# perf_board_schematic.net
KiCad netlist of a schematic drawn in Altium Designer
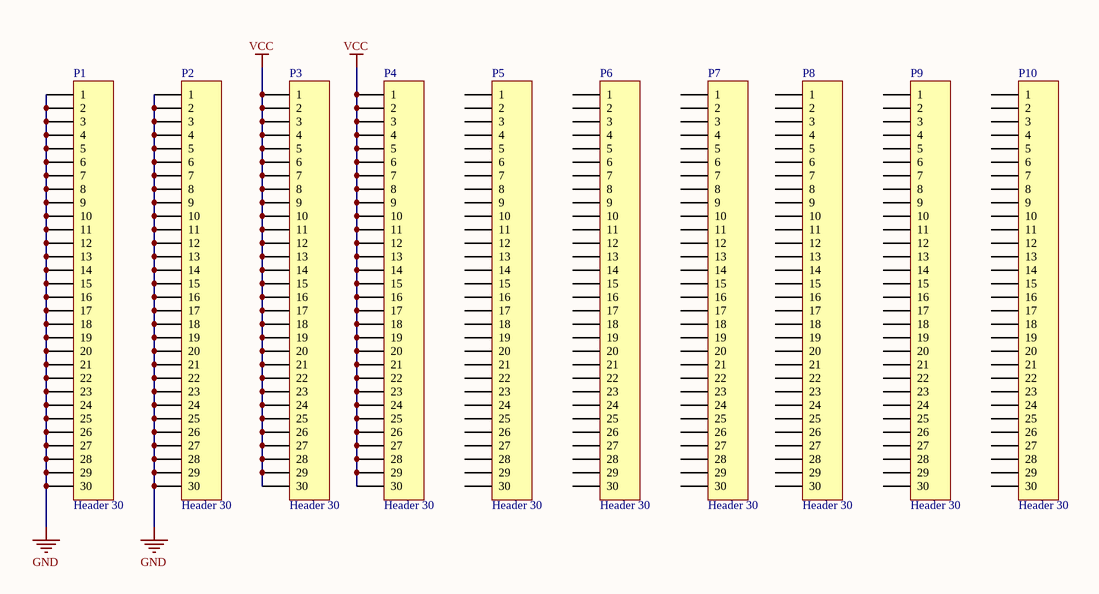
[diagram p0: perf_board_schematic.SchDoc]

(export (version "E")
  (design (tool "Eeschema 10.0.6"))
  (components
    (comp (ref "P1")
      (value "Header 30")
      (footprint "HDR1X30")
      (description "Header, 30-Pin")
      (fields (field (name "PUBLISHER") "Altium Limited"))
      (libsource (lib "Miscellaneous Connectors") (part "Header 30"))
    )
    (comp (ref "P2")
      (value "Header 30")
      (footprint "HDR1X30")
      (description "Header, 30-Pin")
      (fields (field (name "PUBLISHER") "Altium Limited"))
      (libsource (lib "Miscellaneous Connectors") (part "Header 30"))
    )
    (comp (ref "P3")
      (value "Header 30")
      (footprint "HDR1X30")
      (description "Header, 30-Pin")
      (fields (field (name "PUBLISHER") "Altium Limited"))
      (libsource (lib "Miscellaneous Connectors") (part "Header 30"))
    )
    (comp (ref "P4")
      (value "Header 30")
      (footprint "HDR1X30")
      (description "Header, 30-Pin")
      (fields (field (name "PUBLISHER") "Altium Limited"))
      (libsource (lib "Miscellaneous Connectors") (part "Header 30"))
    )
    (comp (ref "P5")
      (value "Header 30")
      (footprint "HDR1X30")
      (description "Header, 30-Pin")
      (fields (field (name "PUBLISHER") "Altium Limited"))
      (libsource (lib "Miscellaneous Connectors") (part "Header 30"))
    )
    (comp (ref "P6")
      (value "Header 30")
      (footprint "HDR1X30")
      (description "Header, 30-Pin")
      (fields (field (name "PUBLISHER") "Altium Limited"))
      (libsource (lib "Miscellaneous Connectors") (part "Header 30"))
    )
    (comp (ref "P7")
      (value "Header 30")
      (footprint "HDR1X30")
      (description "Header, 30-Pin")
      (fields (field (name "PUBLISHER") "Altium Limited"))
      (libsource (lib "Miscellaneous Connectors") (part "Header 30"))
    )
    (comp (ref "P8")
      (value "Header 30")
      (footprint "HDR1X30")
      (description "Header, 30-Pin")
      (fields (field (name "PUBLISHER") "Altium Limited"))
      (libsource (lib "Miscellaneous Connectors") (part "Header 30"))
    )
    (comp (ref "P9")
      (value "Header 30")
      (footprint "HDR1X30")
      (description "Header, 30-Pin")
      (fields (field (name "PUBLISHER") "Altium Limited"))
      (libsource (lib "Miscellaneous Connectors") (part "Header 30"))
    )
    (comp (ref "P10")
      (value "Header 30")
      (footprint "HDR1X30")
      (description "Header, 30-Pin")
      (fields (field (name "PUBLISHER") "Altium Limited"))
      (libsource (lib "Miscellaneous Connectors") (part "Header 30"))
    )
  )
  (nets
    (net (code "1") (name "GND") (class "Default")
      (node (ref "P1") (pin "1") (pinfunction "1_1") (pintype "passive"))
      (node (ref "P1") (pin "10") (pinfunction "10_10") (pintype "passive"))
      (node (ref "P1") (pin "11") (pinfunction "11_11") (pintype "passive"))
      (node (ref "P1") (pin "12") (pinfunction "12_12") (pintype "passive"))
      (node (ref "P1") (pin "13") (pinfunction "13_13") (pintype "passive"))
      (node (ref "P1") (pin "14") (pinfunction "14_14") (pintype "passive"))
      (node (ref "P1") (pin "15") (pinfunction "15_15") (pintype "passive"))
      (node (ref "P1") (pin "16") (pinfunction "16_16") (pintype "passive"))
      (node (ref "P1") (pin "17") (pinfunction "17_17") (pintype "passive"))
      (node (ref "P1") (pin "18") (pinfunction "18_18") (pintype "passive"))
      (node (ref "P1") (pin "19") (pinfunction "19_19") (pintype "passive"))
      (node (ref "P1") (pin "2") (pinfunction "2_2") (pintype "passive"))
      (node (ref "P1") (pin "20") (pinfunction "20_20") (pintype "passive"))
      (node (ref "P1") (pin "21") (pinfunction "21_21") (pintype "passive"))
      (node (ref "P1") (pin "22") (pinfunction "22_22") (pintype "passive"))
      (node (ref "P1") (pin "23") (pinfunction "23_23") (pintype "passive"))
      (node (ref "P1") (pin "24") (pinfunction "24_24") (pintype "passive"))
      (node (ref "P1") (pin "25") (pinfunction "25_25") (pintype "passive"))
      (node (ref "P1") (pin "26") (pinfunction "26_26") (pintype "passive"))
      (node (ref "P1") (pin "27") (pinfunction "27_27") (pintype "passive"))
      (node (ref "P1") (pin "28") (pinfunction "28_28") (pintype "passive"))
      (node (ref "P1") (pin "29") (pinfunction "29_29") (pintype "passive"))
      (node (ref "P1") (pin "3") (pinfunction "3_3") (pintype "passive"))
      (node (ref "P1") (pin "30") (pinfunction "30_30") (pintype "passive"))
      (node (ref "P1") (pin "4") (pinfunction "4_4") (pintype "passive"))
      (node (ref "P1") (pin "5") (pinfunction "5_5") (pintype "passive"))
      (node (ref "P1") (pin "6") (pinfunction "6_6") (pintype "passive"))
      (node (ref "P1") (pin "7") (pinfunction "7_7") (pintype "passive"))
      (node (ref "P1") (pin "8") (pinfunction "8_8") (pintype "passive"))
      (node (ref "P1") (pin "9") (pinfunction "9_9") (pintype "passive"))
      (node (ref "P2") (pin "1") (pinfunction "1_1") (pintype "passive"))
      (node (ref "P2") (pin "10") (pinfunction "10_10") (pintype "passive"))
      (node (ref "P2") (pin "11") (pinfunction "11_11") (pintype "passive"))
      (node (ref "P2") (pin "12") (pinfunction "12_12") (pintype "passive"))
      (node (ref "P2") (pin "13") (pinfunction "13_13") (pintype "passive"))
      (node (ref "P2") (pin "14") (pinfunction "14_14") (pintype "passive"))
      (node (ref "P2") (pin "15") (pinfunction "15_15") (pintype "passive"))
      (node (ref "P2") (pin "16") (pinfunction "16_16") (pintype "passive"))
      (node (ref "P2") (pin "17") (pinfunction "17_17") (pintype "passive"))
      (node (ref "P2") (pin "18") (pinfunction "18_18") (pintype "passive"))
      (node (ref "P2") (pin "19") (pinfunction "19_19") (pintype "passive"))
      (node (ref "P2") (pin "2") (pinfunction "2_2") (pintype "passive"))
      (node (ref "P2") (pin "20") (pinfunction "20_20") (pintype "passive"))
      (node (ref "P2") (pin "21") (pinfunction "21_21") (pintype "passive"))
      (node (ref "P2") (pin "22") (pinfunction "22_22") (pintype "passive"))
      (node (ref "P2") (pin "23") (pinfunction "23_23") (pintype "passive"))
      (node (ref "P2") (pin "24") (pinfunction "24_24") (pintype "passive"))
      (node (ref "P2") (pin "25") (pinfunction "25_25") (pintype "passive"))
      (node (ref "P2") (pin "26") (pinfunction "26_26") (pintype "passive"))
      (node (ref "P2") (pin "27") (pinfunction "27_27") (pintype "passive"))
      (node (ref "P2") (pin "28") (pinfunction "28_28") (pintype "passive"))
      (node (ref "P2") (pin "29") (pinfunction "29_29") (pintype "passive"))
      (node (ref "P2") (pin "3") (pinfunction "3_3") (pintype "passive"))
      (node (ref "P2") (pin "30") (pinfunction "30_30") (pintype "passive"))
      (node (ref "P2") (pin "4") (pinfunction "4_4") (pintype "passive"))
      (node (ref "P2") (pin "5") (pinfunction "5_5") (pintype "passive"))
      (node (ref "P2") (pin "6") (pinfunction "6_6") (pintype "passive"))
      (node (ref "P2") (pin "7") (pinfunction "7_7") (pintype "passive"))
      (node (ref "P2") (pin "8") (pinfunction "8_8") (pintype "passive"))
      (node (ref "P2") (pin "9") (pinfunction "9_9") (pintype "passive"))
    )
    (net (code "2") (name "VCC") (class "Default")
      (node (ref "P3") (pin "1") (pinfunction "1_1") (pintype "passive"))
      (node (ref "P3") (pin "10") (pinfunction "10_10") (pintype "passive"))
      (node (ref "P3") (pin "11") (pinfunction "11_11") (pintype "passive"))
      (node (ref "P3") (pin "12") (pinfunction "12_12") (pintype "passive"))
      (node (ref "P3") (pin "13") (pinfunction "13_13") (pintype "passive"))
      (node (ref "P3") (pin "14") (pinfunction "14_14") (pintype "passive"))
      (node (ref "P3") (pin "15") (pinfunction "15_15") (pintype "passive"))
      (node (ref "P3") (pin "16") (pinfunction "16_16") (pintype "passive"))
      (node (ref "P3") (pin "17") (pinfunction "17_17") (pintype "passive"))
      (node (ref "P3") (pin "18") (pinfunction "18_18") (pintype "passive"))
      (node (ref "P3") (pin "19") (pinfunction "19_19") (pintype "passive"))
      (node (ref "P3") (pin "2") (pinfunction "2_2") (pintype "passive"))
      (node (ref "P3") (pin "20") (pinfunction "20_20") (pintype "passive"))
      (node (ref "P3") (pin "21") (pinfunction "21_21") (pintype "passive"))
      (node (ref "P3") (pin "22") (pinfunction "22_22") (pintype "passive"))
      (node (ref "P3") (pin "23") (pinfunction "23_23") (pintype "passive"))
      (node (ref "P3") (pin "24") (pinfunction "24_24") (pintype "passive"))
      (node (ref "P3") (pin "25") (pinfunction "25_25") (pintype "passive"))
      (node (ref "P3") (pin "26") (pinfunction "26_26") (pintype "passive"))
      (node (ref "P3") (pin "27") (pinfunction "27_27") (pintype "passive"))
      (node (ref "P3") (pin "28") (pinfunction "28_28") (pintype "passive"))
      (node (ref "P3") (pin "29") (pinfunction "29_29") (pintype "passive"))
      (node (ref "P3") (pin "3") (pinfunction "3_3") (pintype "passive"))
      (node (ref "P3") (pin "30") (pinfunction "30_30") (pintype "passive"))
      (node (ref "P3") (pin "4") (pinfunction "4_4") (pintype "passive"))
      (node (ref "P3") (pin "5") (pinfunction "5_5") (pintype "passive"))
      (node (ref "P3") (pin "6") (pinfunction "6_6") (pintype "passive"))
      (node (ref "P3") (pin "7") (pinfunction "7_7") (pintype "passive"))
      (node (ref "P3") (pin "8") (pinfunction "8_8") (pintype "passive"))
      (node (ref "P3") (pin "9") (pinfunction "9_9") (pintype "passive"))
      (node (ref "P4") (pin "1") (pinfunction "1_1") (pintype "passive"))
      (node (ref "P4") (pin "10") (pinfunction "10_10") (pintype "passive"))
      (node (ref "P4") (pin "11") (pinfunction "11_11") (pintype "passive"))
      (node (ref "P4") (pin "12") (pinfunction "12_12") (pintype "passive"))
      (node (ref "P4") (pin "13") (pinfunction "13_13") (pintype "passive"))
      (node (ref "P4") (pin "14") (pinfunction "14_14") (pintype "passive"))
      (node (ref "P4") (pin "15") (pinfunction "15_15") (pintype "passive"))
      (node (ref "P4") (pin "16") (pinfunction "16_16") (pintype "passive"))
      (node (ref "P4") (pin "17") (pinfunction "17_17") (pintype "passive"))
      (node (ref "P4") (pin "18") (pinfunction "18_18") (pintype "passive"))
      (node (ref "P4") (pin "19") (pinfunction "19_19") (pintype "passive"))
      (node (ref "P4") (pin "2") (pinfunction "2_2") (pintype "passive"))
      (node (ref "P4") (pin "20") (pinfunction "20_20") (pintype "passive"))
      (node (ref "P4") (pin "21") (pinfunction "21_21") (pintype "passive"))
      (node (ref "P4") (pin "22") (pinfunction "22_22") (pintype "passive"))
      (node (ref "P4") (pin "23") (pinfunction "23_23") (pintype "passive"))
      (node (ref "P4") (pin "24") (pinfunction "24_24") (pintype "passive"))
      (node (ref "P4") (pin "25") (pinfunction "25_25") (pintype "passive"))
      (node (ref "P4") (pin "26") (pinfunction "26_26") (pintype "passive"))
      (node (ref "P4") (pin "27") (pinfunction "27_27") (pintype "passive"))
      (node (ref "P4") (pin "28") (pinfunction "28_28") (pintype "passive"))
      (node (ref "P4") (pin "29") (pinfunction "29_29") (pintype "passive"))
      (node (ref "P4") (pin "3") (pinfunction "3_3") (pintype "passive"))
      (node (ref "P4") (pin "30") (pinfunction "30_30") (pintype "passive"))
      (node (ref "P4") (pin "4") (pinfunction "4_4") (pintype "passive"))
      (node (ref "P4") (pin "5") (pinfunction "5_5") (pintype "passive"))
      (node (ref "P4") (pin "6") (pinfunction "6_6") (pintype "passive"))
      (node (ref "P4") (pin "7") (pinfunction "7_7") (pintype "passive"))
      (node (ref "P4") (pin "8") (pinfunction "8_8") (pintype "passive"))
      (node (ref "P4") (pin "9") (pinfunction "9_9") (pintype "passive"))
    )
    (net (code "3") (name "unconnected-(P5-Pad1)") (class "Default")
      (node (ref "P5") (pin "1") (pinfunction "1_1") (pintype "passive"))
    )
    (net (code "4") (name "unconnected-(P5-Pad2)") (class "Default")
      (node (ref "P5") (pin "2") (pinfunction "2_2") (pintype "passive"))
    )
    (net (code "5") (name "unconnected-(P5-Pad3)") (class "Default")
      (node (ref "P5") (pin "3") (pinfunction "3_3") (pintype "passive"))
    )
    (net (code "6") (name "unconnected-(P5-Pad4)") (class "Default")
      (node (ref "P5") (pin "4") (pinfunction "4_4") (pintype "passive"))
    )
    (net (code "7") (name "unconnected-(P5-Pad5)") (class "Default")
      (node (ref "P5") (pin "5") (pinfunction "5_5") (pintype "passive"))
    )
    (net (code "8") (name "unconnected-(P5-Pad6)") (class "Default")
      (node (ref "P5") (pin "6") (pinfunction "6_6") (pintype "passive"))
    )
    (net (code "9") (name "unconnected-(P5-Pad7)") (class "Default")
      (node (ref "P5") (pin "7") (pinfunction "7_7") (pintype "passive"))
    )
    (net (code "10") (name "unconnected-(P5-Pad8)") (class "Default")
      (node (ref "P5") (pin "8") (pinfunction "8_8") (pintype "passive"))
    )
    (net (code "11") (name "unconnected-(P5-Pad9)") (class "Default")
      (node (ref "P5") (pin "9") (pinfunction "9_9") (pintype "passive"))
    )
    (net (code "12") (name "unconnected-(P5-Pad10)") (class "Default")
      (node (ref "P5") (pin "10") (pinfunction "10_10") (pintype "passive"))
    )
    (net (code "13") (name "unconnected-(P5-Pad11)") (class "Default")
      (node (ref "P5") (pin "11") (pinfunction "11_11") (pintype "passive"))
    )
    (net (code "14") (name "unconnected-(P5-Pad12)") (class "Default")
      (node (ref "P5") (pin "12") (pinfunction "12_12") (pintype "passive"))
    )
    (net (code "15") (name "unconnected-(P5-Pad13)") (class "Default")
      (node (ref "P5") (pin "13") (pinfunction "13_13") (pintype "passive"))
    )
    (net (code "16") (name "unconnected-(P5-Pad14)") (class "Default")
      (node (ref "P5") (pin "14") (pinfunction "14_14") (pintype "passive"))
    )
    (net (code "17") (name "unconnected-(P5-Pad15)") (class "Default")
      (node (ref "P5") (pin "15") (pinfunction "15_15") (pintype "passive"))
    )
    (net (code "18") (name "unconnected-(P5-Pad16)") (class "Default")
      (node (ref "P5") (pin "16") (pinfunction "16_16") (pintype "passive"))
    )
    (net (code "19") (name "unconnected-(P5-Pad17)") (class "Default")
      (node (ref "P5") (pin "17") (pinfunction "17_17") (pintype "passive"))
    )
    (net (code "20") (name "unconnected-(P5-Pad18)") (class "Default")
      (node (ref "P5") (pin "18") (pinfunction "18_18") (pintype "passive"))
    )
    (net (code "21") (name "unconnected-(P5-Pad19)") (class "Default")
      (node (ref "P5") (pin "19") (pinfunction "19_19") (pintype "passive"))
    )
    (net (code "22") (name "unconnected-(P5-Pad20)") (class "Default")
      (node (ref "P5") (pin "20") (pinfunction "20_20") (pintype "passive"))
    )
    (net (code "23") (name "unconnected-(P5-Pad21)") (class "Default")
      (node (ref "P5") (pin "21") (pinfunction "21_21") (pintype "passive"))
    )
    (net (code "24") (name "unconnected-(P5-Pad22)") (class "Default")
      (node (ref "P5") (pin "22") (pinfunction "22_22") (pintype "passive"))
    )
    (net (code "25") (name "unconnected-(P5-Pad23)") (class "Default")
      (node (ref "P5") (pin "23") (pinfunction "23_23") (pintype "passive"))
    )
    (net (code "26") (name "unconnected-(P5-Pad24)") (class "Default")
      (node (ref "P5") (pin "24") (pinfunction "24_24") (pintype "passive"))
    )
    (net (code "27") (name "unconnected-(P5-Pad25)") (class "Default")
      (node (ref "P5") (pin "25") (pinfunction "25_25") (pintype "passive"))
    )
    (net (code "28") (name "unconnected-(P5-Pad26)") (class "Default")
      (node (ref "P5") (pin "26") (pinfunction "26_26") (pintype "passive"))
    )
    (net (code "29") (name "unconnected-(P5-Pad27)") (class "Default")
      (node (ref "P5") (pin "27") (pinfunction "27_27") (pintype "passive"))
    )
    (net (code "30") (name "unconnected-(P5-Pad28)") (class "Default")
      (node (ref "P5") (pin "28") (pinfunction "28_28") (pintype "passive"))
    )
    (net (code "31") (name "unconnected-(P5-Pad29)") (class "Default")
      (node (ref "P5") (pin "29") (pinfunction "29_29") (pintype "passive"))
    )
    (net (code "32") (name "unconnected-(P5-Pad30)") (class "Default")
      (node (ref "P5") (pin "30") (pinfunction "30_30") (pintype "passive"))
    )
    (net (code "33") (name "unconnected-(P6-Pad1)") (class "Default")
      (node (ref "P6") (pin "1") (pinfunction "1_1") (pintype "passive"))
    )
    (net (code "34") (name "unconnected-(P6-Pad2)") (class "Default")
      (node (ref "P6") (pin "2") (pinfunction "2_2") (pintype "passive"))
    )
    (net (code "35") (name "unconnected-(P6-Pad3)") (class "Default")
      (node (ref "P6") (pin "3") (pinfunction "3_3") (pintype "passive"))
    )
    (net (code "36") (name "unconnected-(P6-Pad4)") (class "Default")
      (node (ref "P6") (pin "4") (pinfunction "4_4") (pintype "passive"))
    )
    (net (code "37") (name "unconnected-(P6-Pad5)") (class "Default")
      (node (ref "P6") (pin "5") (pinfunction "5_5") (pintype "passive"))
    )
    (net (code "38") (name "unconnected-(P6-Pad6)") (class "Default")
      (node (ref "P6") (pin "6") (pinfunction "6_6") (pintype "passive"))
    )
    (net (code "39") (name "unconnected-(P6-Pad7)") (class "Default")
      (node (ref "P6") (pin "7") (pinfunction "7_7") (pintype "passive"))
    )
    (net (code "40") (name "unconnected-(P6-Pad8)") (class "Default")
      (node (ref "P6") (pin "8") (pinfunction "8_8") (pintype "passive"))
    )
    (net (code "41") (name "unconnected-(P6-Pad9)") (class "Default")
      (node (ref "P6") (pin "9") (pinfunction "9_9") (pintype "passive"))
    )
    (net (code "42") (name "unconnected-(P6-Pad10)") (class "Default")
      (node (ref "P6") (pin "10") (pinfunction "10_10") (pintype "passive"))
    )
    (net (code "43") (name "unconnected-(P6-Pad11)") (class "Default")
      (node (ref "P6") (pin "11") (pinfunction "11_11") (pintype "passive"))
    )
    (net (code "44") (name "unconnected-(P6-Pad12)") (class "Default")
      (node (ref "P6") (pin "12") (pinfunction "12_12") (pintype "passive"))
    )
    (net (code "45") (name "unconnected-(P6-Pad13)") (class "Default")
      (node (ref "P6") (pin "13") (pinfunction "13_13") (pintype "passive"))
    )
    (net (code "46") (name "unconnected-(P6-Pad14)") (class "Default")
      (node (ref "P6") (pin "14") (pinfunction "14_14") (pintype "passive"))
    )
    (net (code "47") (name "unconnected-(P6-Pad15)") (class "Default")
      (node (ref "P6") (pin "15") (pinfunction "15_15") (pintype "passive"))
    )
    (net (code "48") (name "unconnected-(P6-Pad16)") (class "Default")
      (node (ref "P6") (pin "16") (pinfunction "16_16") (pintype "passive"))
    )
    (net (code "49") (name "unconnected-(P6-Pad17)") (class "Default")
      (node (ref "P6") (pin "17") (pinfunction "17_17") (pintype "passive"))
    )
    (net (code "50") (name "unconnected-(P6-Pad18)") (class "Default")
      (node (ref "P6") (pin "18") (pinfunction "18_18") (pintype "passive"))
    )
    (net (code "51") (name "unconnected-(P6-Pad19)") (class "Default")
      (node (ref "P6") (pin "19") (pinfunction "19_19") (pintype "passive"))
    )
    (net (code "52") (name "unconnected-(P6-Pad20)") (class "Default")
      (node (ref "P6") (pin "20") (pinfunction "20_20") (pintype "passive"))
    )
    (net (code "53") (name "unconnected-(P6-Pad21)") (class "Default")
      (node (ref "P6") (pin "21") (pinfunction "21_21") (pintype "passive"))
    )
    (net (code "54") (name "unconnected-(P6-Pad22)") (class "Default")
      (node (ref "P6") (pin "22") (pinfunction "22_22") (pintype "passive"))
    )
    (net (code "55") (name "unconnected-(P6-Pad23)") (class "Default")
      (node (ref "P6") (pin "23") (pinfunction "23_23") (pintype "passive"))
    )
    (net (code "56") (name "unconnected-(P6-Pad24)") (class "Default")
      (node (ref "P6") (pin "24") (pinfunction "24_24") (pintype "passive"))
    )
    (net (code "57") (name "unconnected-(P6-Pad25)") (class "Default")
      (node (ref "P6") (pin "25") (pinfunction "25_25") (pintype "passive"))
    )
    (net (code "58") (name "unconnected-(P6-Pad26)") (class "Default")
      (node (ref "P6") (pin "26") (pinfunction "26_26") (pintype "passive"))
    )
    (net (code "59") (name "unconnected-(P6-Pad27)") (class "Default")
      (node (ref "P6") (pin "27") (pinfunction "27_27") (pintype "passive"))
    )
    (net (code "60") (name "unconnected-(P6-Pad28)") (class "Default")
      (node (ref "P6") (pin "28") (pinfunction "28_28") (pintype "passive"))
    )
    (net (code "61") (name "unconnected-(P6-Pad29)") (class "Default")
      (node (ref "P6") (pin "29") (pinfunction "29_29") (pintype "passive"))
    )
    (net (code "62") (name "unconnected-(P6-Pad30)") (class "Default")
      (node (ref "P6") (pin "30") (pinfunction "30_30") (pintype "passive"))
    )
    (net (code "63") (name "unconnected-(P7-Pad1)") (class "Default")
      (node (ref "P7") (pin "1") (pinfunction "1_1") (pintype "passive"))
    )
    (net (code "64") (name "unconnected-(P7-Pad2)") (class "Default")
      (node (ref "P7") (pin "2") (pinfunction "2_2") (pintype "passive"))
    )
    (net (code "65") (name "unconnected-(P7-Pad3)") (class "Default")
      (node (ref "P7") (pin "3") (pinfunction "3_3") (pintype "passive"))
    )
    (net (code "66") (name "unconnected-(P7-Pad4)") (class "Default")
      (node (ref "P7") (pin "4") (pinfunction "4_4") (pintype "passive"))
    )
    (net (code "67") (name "unconnected-(P7-Pad5)") (class "Default")
      (node (ref "P7") (pin "5") (pinfunction "5_5") (pintype "passive"))
    )
    (net (code "68") (name "unconnected-(P7-Pad6)") (class "Default")
      (node (ref "P7") (pin "6") (pinfunction "6_6") (pintype "passive"))
    )
    (net (code "69") (name "unconnected-(P7-Pad7)") (class "Default")
      (node (ref "P7") (pin "7") (pinfunction "7_7") (pintype "passive"))
    )
    (net (code "70") (name "unconnected-(P7-Pad8)") (class "Default")
      (node (ref "P7") (pin "8") (pinfunction "8_8") (pintype "passive"))
    )
    (net (code "71") (name "unconnected-(P7-Pad9)") (class "Default")
      (node (ref "P7") (pin "9") (pinfunction "9_9") (pintype "passive"))
    )
    (net (code "72") (name "unconnected-(P7-Pad10)") (class "Default")
      (node (ref "P7") (pin "10") (pinfunction "10_10") (pintype "passive"))
    )
    (net (code "73") (name "unconnected-(P7-Pad11)") (class "Default")
      (node (ref "P7") (pin "11") (pinfunction "11_11") (pintype "passive"))
    )
    (net (code "74") (name "unconnected-(P7-Pad12)") (class "Default")
      (node (ref "P7") (pin "12") (pinfunction "12_12") (pintype "passive"))
    )
    (net (code "75") (name "unconnected-(P7-Pad13)") (class "Default")
      (node (ref "P7") (pin "13") (pinfunction "13_13") (pintype "passive"))
    )
    (net (code "76") (name "unconnected-(P7-Pad14)") (class "Default")
      (node (ref "P7") (pin "14") (pinfunction "14_14") (pintype "passive"))
    )
    (net (code "77") (name "unconnected-(P7-Pad15)") (class "Default")
      (node (ref "P7") (pin "15") (pinfunction "15_15") (pintype "passive"))
    )
    (net (code "78") (name "unconnected-(P7-Pad16)") (class "Default")
      (node (ref "P7") (pin "16") (pinfunction "16_16") (pintype "passive"))
    )
    (net (code "79") (name "unconnected-(P7-Pad17)") (class "Default")
      (node (ref "P7") (pin "17") (pinfunction "17_17") (pintype "passive"))
    )
    (net (code "80") (name "unconnected-(P7-Pad18)") (class "Default")
      (node (ref "P7") (pin "18") (pinfunction "18_18") (pintype "passive"))
    )
    (net (code "81") (name "unconnected-(P7-Pad19)") (class "Default")
      (node (ref "P7") (pin "19") (pinfunction "19_19") (pintype "passive"))
    )
    (net (code "82") (name "unconnected-(P7-Pad20)") (class "Default")
      (node (ref "P7") (pin "20") (pinfunction "20_20") (pintype "passive"))
    )
    (net (code "83") (name "unconnected-(P7-Pad21)") (class "Default")
      (node (ref "P7") (pin "21") (pinfunction "21_21") (pintype "passive"))
    )
    (net (code "84") (name "unconnected-(P7-Pad22)") (class "Default")
      (node (ref "P7") (pin "22") (pinfunction "22_22") (pintype "passive"))
    )
    (net (code "85") (name "unconnected-(P7-Pad23)") (class "Default")
      (node (ref "P7") (pin "23") (pinfunction "23_23") (pintype "passive"))
    )
    (net (code "86") (name "unconnected-(P7-Pad24)") (class "Default")
      (node (ref "P7") (pin "24") (pinfunction "24_24") (pintype "passive"))
    )
    (net (code "87") (name "unconnected-(P7-Pad25)") (class "Default")
      (node (ref "P7") (pin "25") (pinfunction "25_25") (pintype "passive"))
    )
    (net (code "88") (name "unconnected-(P7-Pad26)") (class "Default")
      (node (ref "P7") (pin "26") (pinfunction "26_26") (pintype "passive"))
    )
    (net (code "89") (name "unconnected-(P7-Pad27)") (class "Default")
      (node (ref "P7") (pin "27") (pinfunction "27_27") (pintype "passive"))
    )
    (net (code "90") (name "unconnected-(P7-Pad28)") (class "Default")
      (node (ref "P7") (pin "28") (pinfunction "28_28") (pintype "passive"))
    )
    (net (code "91") (name "unconnected-(P7-Pad29)") (class "Default")
      (node (ref "P7") (pin "29") (pinfunction "29_29") (pintype "passive"))
    )
    (net (code "92") (name "unconnected-(P7-Pad30)") (class "Default")
      (node (ref "P7") (pin "30") (pinfunction "30_30") (pintype "passive"))
    )
    (net (code "93") (name "unconnected-(P8-Pad1)") (class "Default")
      (node (ref "P8") (pin "1") (pinfunction "1_1") (pintype "passive"))
    )
    (net (code "94") (name "unconnected-(P8-Pad2)") (class "Default")
      (node (ref "P8") (pin "2") (pinfunction "2_2") (pintype "passive"))
    )
    (net (code "95") (name "unconnected-(P8-Pad3)") (class "Default")
      (node (ref "P8") (pin "3") (pinfunction "3_3") (pintype "passive"))
    )
    (net (code "96") (name "unconnected-(P8-Pad4)") (class "Default")
      (node (ref "P8") (pin "4") (pinfunction "4_4") (pintype "passive"))
    )
    (net (code "97") (name "unconnected-(P8-Pad5)") (class "Default")
      (node (ref "P8") (pin "5") (pinfunction "5_5") (pintype "passive"))
    )
    (net (code "98") (name "unconnected-(P8-Pad6)") (class "Default")
      (node (ref "P8") (pin "6") (pinfunction "6_6") (pintype "passive"))
    )
    (net (code "99") (name "unconnected-(P8-Pad7)") (class "Default")
      (node (ref "P8") (pin "7") (pinfunction "7_7") (pintype "passive"))
    )
    (net (code "100") (name "unconnected-(P8-Pad8)") (class "Default")
      (node (ref "P8") (pin "8") (pinfunction "8_8") (pintype "passive"))
    )
    (net (code "101") (name "unconnected-(P8-Pad9)") (class "Default")
      (node (ref "P8") (pin "9") (pinfunction "9_9") (pintype "passive"))
    )
    (net (code "102") (name "unconnected-(P8-Pad10)") (class "Default")
      (node (ref "P8") (pin "10") (pinfunction "10_10") (pintype "passive"))
    )
    (net (code "103") (name "unconnected-(P8-Pad11)") (class "Default")
      (node (ref "P8") (pin "11") (pinfunction "11_11") (pintype "passive"))
    )
    (net (code "104") (name "unconnected-(P8-Pad12)") (class "Default")
      (node (ref "P8") (pin "12") (pinfunction "12_12") (pintype "passive"))
    )
    (net (code "105") (name "unconnected-(P8-Pad13)") (class "Default")
      (node (ref "P8") (pin "13") (pinfunction "13_13") (pintype "passive"))
    )
    (net (code "106") (name "unconnected-(P8-Pad14)") (class "Default")
      (node (ref "P8") (pin "14") (pinfunction "14_14") (pintype "passive"))
    )
    (net (code "107") (name "unconnected-(P8-Pad15)") (class "Default")
      (node (ref "P8") (pin "15") (pinfunction "15_15") (pintype "passive"))
    )
    (net (code "108") (name "unconnected-(P8-Pad16)") (class "Default")
      (node (ref "P8") (pin "16") (pinfunction "16_16") (pintype "passive"))
    )
    (net (code "109") (name "unconnected-(P8-Pad17)") (class "Default")
      (node (ref "P8") (pin "17") (pinfunction "17_17") (pintype "passive"))
    )
    (net (code "110") (name "unconnected-(P8-Pad18)") (class "Default")
      (node (ref "P8") (pin "18") (pinfunction "18_18") (pintype "passive"))
    )
    (net (code "111") (name "unconnected-(P8-Pad19)") (class "Default")
      (node (ref "P8") (pin "19") (pinfunction "19_19") (pintype "passive"))
    )
    (net (code "112") (name "unconnected-(P8-Pad20)") (class "Default")
      (node (ref "P8") (pin "20") (pinfunction "20_20") (pintype "passive"))
    )
    (net (code "113") (name "unconnected-(P8-Pad21)") (class "Default")
      (node (ref "P8") (pin "21") (pinfunction "21_21") (pintype "passive"))
    )
    (net (code "114") (name "unconnected-(P8-Pad22)") (class "Default")
      (node (ref "P8") (pin "22") (pinfunction "22_22") (pintype "passive"))
    )
    (net (code "115") (name "unconnected-(P8-Pad23)") (class "Default")
      (node (ref "P8") (pin "23") (pinfunction "23_23") (pintype "passive"))
    )
    (net (code "116") (name "unconnected-(P8-Pad24)") (class "Default")
      (node (ref "P8") (pin "24") (pinfunction "24_24") (pintype "passive"))
    )
    (net (code "117") (name "unconnected-(P8-Pad25)") (class "Default")
      (node (ref "P8") (pin "25") (pinfunction "25_25") (pintype "passive"))
    )
    (net (code "118") (name "unconnected-(P8-Pad26)") (class "Default")
      (node (ref "P8") (pin "26") (pinfunction "26_26") (pintype "passive"))
    )
    (net (code "119") (name "unconnected-(P8-Pad27)") (class "Default")
      (node (ref "P8") (pin "27") (pinfunction "27_27") (pintype "passive"))
    )
    (net (code "120") (name "unconnected-(P8-Pad28)") (class "Default")
      (node (ref "P8") (pin "28") (pinfunction "28_28") (pintype "passive"))
    )
    (net (code "121") (name "unconnected-(P8-Pad29)") (class "Default")
      (node (ref "P8") (pin "29") (pinfunction "29_29") (pintype "passive"))
    )
    (net (code "122") (name "unconnected-(P8-Pad30)") (class "Default")
      (node (ref "P8") (pin "30") (pinfunction "30_30") (pintype "passive"))
    )
    (net (code "123") (name "unconnected-(P9-Pad1)") (class "Default")
      (node (ref "P9") (pin "1") (pinfunction "1_1") (pintype "passive"))
    )
    (net (code "124") (name "unconnected-(P9-Pad2)") (class "Default")
      (node (ref "P9") (pin "2") (pinfunction "2_2") (pintype "passive"))
    )
    (net (code "125") (name "unconnected-(P9-Pad3)") (class "Default")
      (node (ref "P9") (pin "3") (pinfunction "3_3") (pintype "passive"))
    )
    (net (code "126") (name "unconnected-(P9-Pad4)") (class "Default")
      (node (ref "P9") (pin "4") (pinfunction "4_4") (pintype "passive"))
    )
    (net (code "127") (name "unconnected-(P9-Pad5)") (class "Default")
      (node (ref "P9") (pin "5") (pinfunction "5_5") (pintype "passive"))
    )
    (net (code "128") (name "unconnected-(P9-Pad6)") (class "Default")
      (node (ref "P9") (pin "6") (pinfunction "6_6") (pintype "passive"))
    )
    (net (code "129") (name "unconnected-(P9-Pad7)") (class "Default")
      (node (ref "P9") (pin "7") (pinfunction "7_7") (pintype "passive"))
    )
    (net (code "130") (name "unconnected-(P9-Pad8)") (class "Default")
      (node (ref "P9") (pin "8") (pinfunction "8_8") (pintype "passive"))
    )
    (net (code "131") (name "unconnected-(P9-Pad9)") (class "Default")
      (node (ref "P9") (pin "9") (pinfunction "9_9") (pintype "passive"))
    )
    (net (code "132") (name "unconnected-(P9-Pad10)") (class "Default")
      (node (ref "P9") (pin "10") (pinfunction "10_10") (pintype "passive"))
    )
    (net (code "133") (name "unconnected-(P9-Pad11)") (class "Default")
      (node (ref "P9") (pin "11") (pinfunction "11_11") (pintype "passive"))
    )
    (net (code "134") (name "unconnected-(P9-Pad12)") (class "Default")
      (node (ref "P9") (pin "12") (pinfunction "12_12") (pintype "passive"))
    )
    (net (code "135") (name "unconnected-(P9-Pad13)") (class "Default")
      (node (ref "P9") (pin "13") (pinfunction "13_13") (pintype "passive"))
    )
    (net (code "136") (name "unconnected-(P9-Pad14)") (class "Default")
      (node (ref "P9") (pin "14") (pinfunction "14_14") (pintype "passive"))
    )
    (net (code "137") (name "unconnected-(P9-Pad15)") (class "Default")
      (node (ref "P9") (pin "15") (pinfunction "15_15") (pintype "passive"))
    )
    (net (code "138") (name "unconnected-(P9-Pad16)") (class "Default")
      (node (ref "P9") (pin "16") (pinfunction "16_16") (pintype "passive"))
    )
    (net (code "139") (name "unconnected-(P9-Pad17)") (class "Default")
      (node (ref "P9") (pin "17") (pinfunction "17_17") (pintype "passive"))
    )
    (net (code "140") (name "unconnected-(P9-Pad18)") (class "Default")
      (node (ref "P9") (pin "18") (pinfunction "18_18") (pintype "passive"))
    )
    (net (code "141") (name "unconnected-(P9-Pad19)") (class "Default")
      (node (ref "P9") (pin "19") (pinfunction "19_19") (pintype "passive"))
    )
    (net (code "142") (name "unconnected-(P9-Pad20)") (class "Default")
      (node (ref "P9") (pin "20") (pinfunction "20_20") (pintype "passive"))
    )
    (net (code "143") (name "unconnected-(P9-Pad21)") (class "Default")
      (node (ref "P9") (pin "21") (pinfunction "21_21") (pintype "passive"))
    )
    (net (code "144") (name "unconnected-(P9-Pad22)") (class "Default")
      (node (ref "P9") (pin "22") (pinfunction "22_22") (pintype "passive"))
    )
    (net (code "145") (name "unconnected-(P9-Pad23)") (class "Default")
      (node (ref "P9") (pin "23") (pinfunction "23_23") (pintype "passive"))
    )
    (net (code "146") (name "unconnected-(P9-Pad24)") (class "Default")
      (node (ref "P9") (pin "24") (pinfunction "24_24") (pintype "passive"))
    )
    (net (code "147") (name "unconnected-(P9-Pad25)") (class "Default")
      (node (ref "P9") (pin "25") (pinfunction "25_25") (pintype "passive"))
    )
    (net (code "148") (name "unconnected-(P9-Pad26)") (class "Default")
      (node (ref "P9") (pin "26") (pinfunction "26_26") (pintype "passive"))
    )
    (net (code "149") (name "unconnected-(P9-Pad27)") (class "Default")
      (node (ref "P9") (pin "27") (pinfunction "27_27") (pintype "passive"))
    )
    (net (code "150") (name "unconnected-(P9-Pad28)") (class "Default")
      (node (ref "P9") (pin "28") (pinfunction "28_28") (pintype "passive"))
    )
    (net (code "151") (name "unconnected-(P9-Pad29)") (class "Default")
      (node (ref "P9") (pin "29") (pinfunction "29_29") (pintype "passive"))
    )
    (net (code "152") (name "unconnected-(P9-Pad30)") (class "Default")
      (node (ref "P9") (pin "30") (pinfunction "30_30") (pintype "passive"))
    )
    (net (code "153") (name "unconnected-(P10-Pad1)") (class "Default")
      (node (ref "P10") (pin "1") (pinfunction "1_1") (pintype "passive"))
    )
    (net (code "154") (name "unconnected-(P10-Pad2)") (class "Default")
      (node (ref "P10") (pin "2") (pinfunction "2_2") (pintype "passive"))
    )
    (net (code "155") (name "unconnected-(P10-Pad3)") (class "Default")
      (node (ref "P10") (pin "3") (pinfunction "3_3") (pintype "passive"))
    )
    (net (code "156") (name "unconnected-(P10-Pad4)") (class "Default")
      (node (ref "P10") (pin "4") (pinfunction "4_4") (pintype "passive"))
    )
    (net (code "157") (name "unconnected-(P10-Pad5)") (class "Default")
      (node (ref "P10") (pin "5") (pinfunction "5_5") (pintype "passive"))
    )
    (net (code "158") (name "unconnected-(P10-Pad6)") (class "Default")
      (node (ref "P10") (pin "6") (pinfunction "6_6") (pintype "passive"))
    )
    (net (code "159") (name "unconnected-(P10-Pad7)") (class "Default")
      (node (ref "P10") (pin "7") (pinfunction "7_7") (pintype "passive"))
    )
    (net (code "160") (name "unconnected-(P10-Pad8)") (class "Default")
      (node (ref "P10") (pin "8") (pinfunction "8_8") (pintype "passive"))
    )
    (net (code "161") (name "unconnected-(P10-Pad9)") (class "Default")
      (node (ref "P10") (pin "9") (pinfunction "9_9") (pintype "passive"))
    )
    (net (code "162") (name "unconnected-(P10-Pad10)") (class "Default")
      (node (ref "P10") (pin "10") (pinfunction "10_10") (pintype "passive"))
    )
    (net (code "163") (name "unconnected-(P10-Pad11)") (class "Default")
      (node (ref "P10") (pin "11") (pinfunction "11_11") (pintype "passive"))
    )
    (net (code "164") (name "unconnected-(P10-Pad12)") (class "Default")
      (node (ref "P10") (pin "12") (pinfunction "12_12") (pintype "passive"))
    )
    (net (code "165") (name "unconnected-(P10-Pad13)") (class "Default")
      (node (ref "P10") (pin "13") (pinfunction "13_13") (pintype "passive"))
    )
    (net (code "166") (name "unconnected-(P10-Pad14)") (class "Default")
      (node (ref "P10") (pin "14") (pinfunction "14_14") (pintype "passive"))
    )
    (net (code "167") (name "unconnected-(P10-Pad15)") (class "Default")
      (node (ref "P10") (pin "15") (pinfunction "15_15") (pintype "passive"))
    )
    (net (code "168") (name "unconnected-(P10-Pad16)") (class "Default")
      (node (ref "P10") (pin "16") (pinfunction "16_16") (pintype "passive"))
    )
    (net (code "169") (name "unconnected-(P10-Pad17)") (class "Default")
      (node (ref "P10") (pin "17") (pinfunction "17_17") (pintype "passive"))
    )
    (net (code "170") (name "unconnected-(P10-Pad18)") (class "Default")
      (node (ref "P10") (pin "18") (pinfunction "18_18") (pintype "passive"))
    )
    (net (code "171") (name "unconnected-(P10-Pad19)") (class "Default")
      (node (ref "P10") (pin "19") (pinfunction "19_19") (pintype "passive"))
    )
    (net (code "172") (name "unconnected-(P10-Pad20)") (class "Default")
      (node (ref "P10") (pin "20") (pinfunction "20_20") (pintype "passive"))
    )
    (net (code "173") (name "unconnected-(P10-Pad21)") (class "Default")
      (node (ref "P10") (pin "21") (pinfunction "21_21") (pintype "passive"))
    )
    (net (code "174") (name "unconnected-(P10-Pad22)") (class "Default")
      (node (ref "P10") (pin "22") (pinfunction "22_22") (pintype "passive"))
    )
    (net (code "175") (name "unconnected-(P10-Pad23)") (class "Default")
      (node (ref "P10") (pin "23") (pinfunction "23_23") (pintype "passive"))
    )
    (net (code "176") (name "unconnected-(P10-Pad24)") (class "Default")
      (node (ref "P10") (pin "24") (pinfunction "24_24") (pintype "passive"))
    )
    (net (code "177") (name "unconnected-(P10-Pad25)") (class "Default")
      (node (ref "P10") (pin "25") (pinfunction "25_25") (pintype "passive"))
    )
    (net (code "178") (name "unconnected-(P10-Pad26)") (class "Default")
      (node (ref "P10") (pin "26") (pinfunction "26_26") (pintype "passive"))
    )
    (net (code "179") (name "unconnected-(P10-Pad27)") (class "Default")
      (node (ref "P10") (pin "27") (pinfunction "27_27") (pintype "passive"))
    )
    (net (code "180") (name "unconnected-(P10-Pad28)") (class "Default")
      (node (ref "P10") (pin "28") (pinfunction "28_28") (pintype "passive"))
    )
    (net (code "181") (name "unconnected-(P10-Pad29)") (class "Default")
      (node (ref "P10") (pin "29") (pinfunction "29_29") (pintype "passive"))
    )
    (net (code "182") (name "unconnected-(P10-Pad30)") (class "Default")
      (node (ref "P10") (pin "30") (pinfunction "30_30") (pintype "passive"))
    )
  )
)
